# ShieldArduino_Due_5.net
KiCad netlist of a schematic drawn in Altium Designer
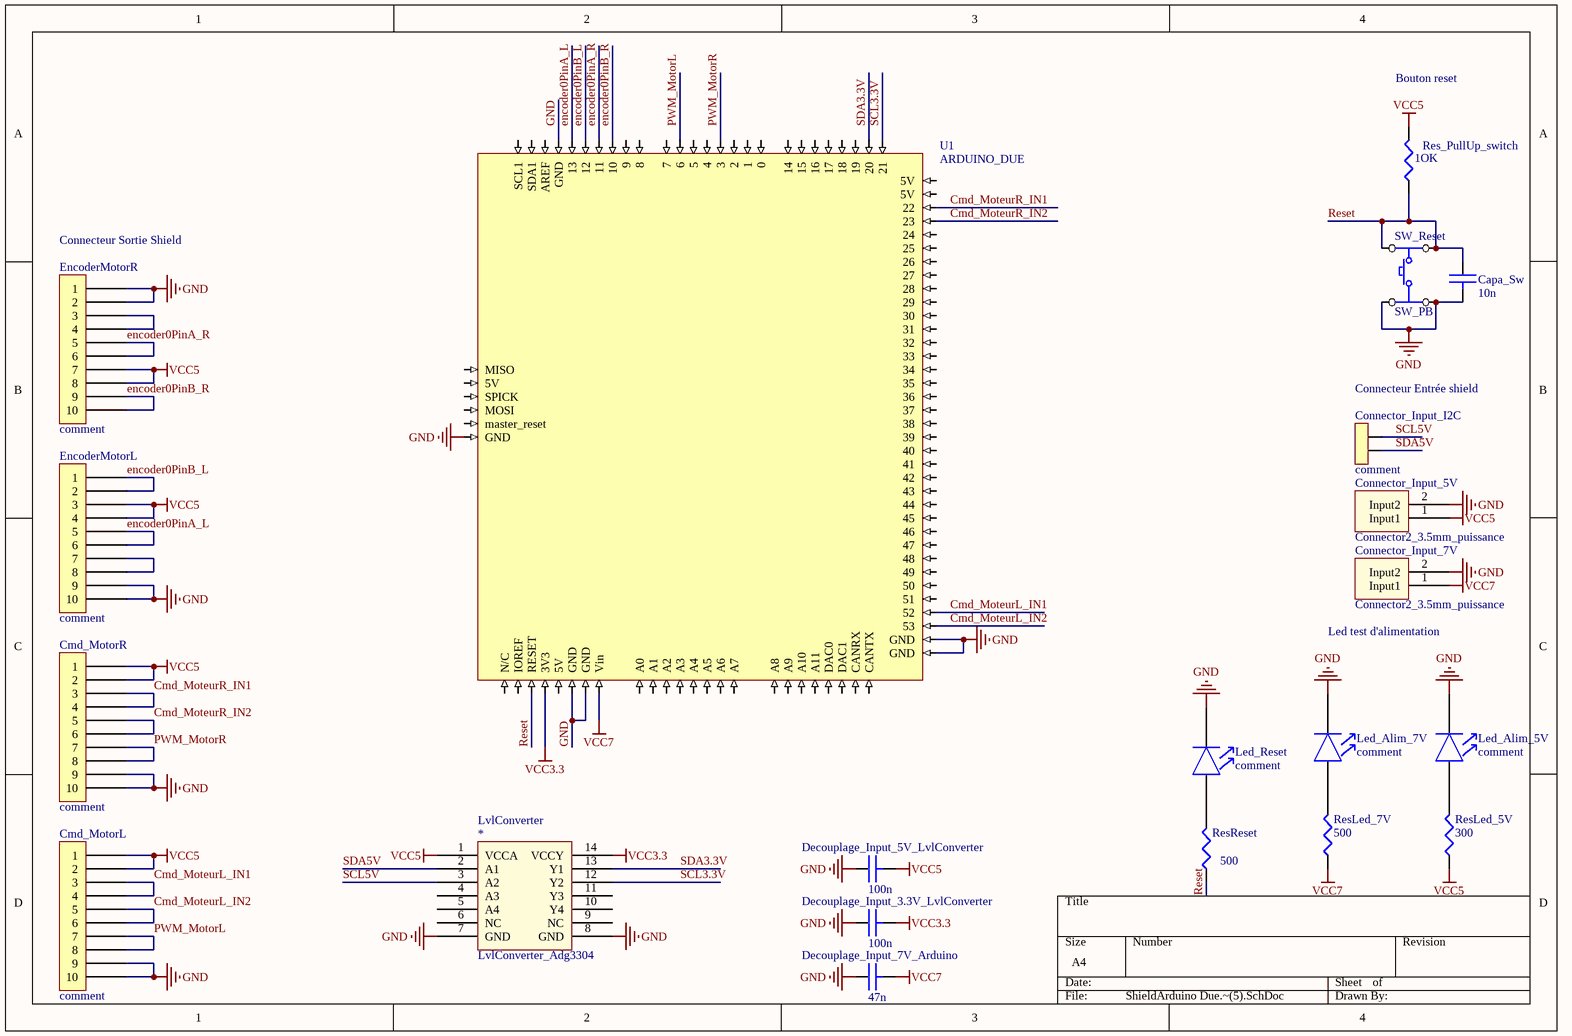
[diagram p0: ShieldArduino Due.~(5).SchDoc]

(export (version "E")
  (design (tool "Eeschema 10.0.6"))
  (components
    (comp (ref "*")
      (value "LvlConverter_Adg3304")
      (footprint "LvlConverter_Adg3304")
      (libsource (lib "LvlConverter_Adg3304") (part "LvlConverter_Adg3304"))
    )
    (comp (ref "Capa_Sw")
      (value "10n")
      (footprint "0805")
      (description "capacité non polarisée")
      (fields (field (name "Comment") "CAP"))
      (libsource (lib "ISEN_basics") (part "CAP"))
    )
    (comp (ref "Cmd_MotorL")
      (value "comment")
      (footprint "HE10-10V")
      (description "10-pin connector")
      (libsource (lib "ISEN_basics") (part "HE10-10"))
    )
    (comp (ref "Cmd_MotorR")
      (value "comment")
      (footprint "HE10-10V")
      (description "10-pin connector")
      (libsource (lib "ISEN_basics") (part "HE10-10"))
    )
    (comp (ref "Connector_Input_5V")
      (value "Connector2_3.5mm_puissance")
      (footprint "Connector2_3.5mm_puissance")
      (libsource (lib "Connector2_3.5mm_puissance") (part "Connector2_3.5mm_puissance"))
    )
    (comp (ref "Connector_Input_7V")
      (value "Connector2_3.5mm_puissance")
      (footprint "Connector2_3.5mm_puissance")
      (libsource (lib "Connector2_3.5mm_puissance") (part "Connector2_3.5mm_puissance"))
    )
    (comp (ref "Connector_Input_I2C")
      (value "comment")
      (footprint "AMP_2")
      (description "connecteur alim 2 pôles")
      (libsource (lib "ISEN_basics") (part "POWER2"))
    )
    (comp (ref "Decouplage_Input_3.3V_LvlConverter")
      (value "100n")
      (footprint "0805")
      (description "capacité non polarisée")
      (fields (field (name "Comment") "CAP"))
      (libsource (lib "ISEN_basics") (part "CAP"))
    )
    (comp (ref "Decouplage_Input_5V_LvlConverter")
      (value "100n")
      (footprint "0805")
      (description "capacité non polarisée")
      (fields (field (name "Comment") "CAP"))
      (libsource (lib "ISEN_basics") (part "CAP"))
    )
    (comp (ref "Decouplage_Input_7V_Arduino")
      (value "47n")
      (footprint "0805")
      (description "capacité non polarisée")
      (fields (field (name "Comment") "CAP"))
      (libsource (lib "ISEN_basics") (part "CAP"))
    )
    (comp (ref "EncoderMotorL")
      (value "comment")
      (footprint "HE10-10V")
      (description "10-pin connector")
      (libsource (lib "ISEN_basics") (part "HE10-10"))
    )
    (comp (ref "EncoderMotorR")
      (value "comment")
      (footprint "HE10-10V")
      (description "10-pin connector")
      (libsource (lib "ISEN_basics") (part "HE10-10"))
    )
    (comp (ref "Led_Alim_5V")
      (value "comment")
      (footprint "LED0805")
      (description "LED 5mm/3mm/CMS")
      (libsource (lib "ISEN_basics") (part "LED"))
    )
    (comp (ref "Led_Alim_7V")
      (value "comment")
      (footprint "LED0805")
      (description "LED 5mm/3mm/CMS")
      (libsource (lib "ISEN_basics") (part "LED"))
    )
    (comp (ref "Led_Reset")
      (value "comment")
      (footprint "LED0805")
      (description "LED 5mm/3mm/CMS")
      (libsource (lib "ISEN_basics") (part "LED"))
    )
    (comp (ref "ResLed_5V")
      (value "300")
      (footprint "0805")
      (description "resistance")
      (fields (field (name "Comment") "RES"))
      (libsource (lib "ISEN_basics") (part "RES"))
    )
    (comp (ref "ResLed_7V")
      (value "500")
      (footprint "0805")
      (description "resistance")
      (fields (field (name "Comment") "RES"))
      (libsource (lib "ISEN_basics") (part "RES"))
    )
    (comp (ref "ResReset")
      (value "500")
      (footprint "0805")
      (description "resistance")
      (fields (field (name "Comment") "RES"))
      (libsource (lib "ISEN_basics") (part "RES"))
    )
    (comp (ref "Res_PullUp_switch")
      (value "1OK")
      (footprint "0805")
      (description "resistance")
      (fields (field (name "Comment") "RES"))
      (libsource (lib "ISEN_basics") (part "RES"))
    )
    (comp (ref "SW_Reset") (value "SW_PB") (footprint "KSA") (libsource (lib "ISEN_basics") (part "SW_PB")))
    (comp (ref "U1")
      (value "ARDUINO_DUE")
      (footprint "ARDUINO_DUE")
      (libsource (lib "ISEN_basics") (part "ARDUINO_DUE"))
    )
  )
  (nets
    (net (code "1") (name "/Cmd_MoteurL_IN1") (class "Default")
      (node (ref "Cmd_MotorL") (pin "3") (pinfunction "3_3") (pintype "passive"))
      (node (ref "Cmd_MotorL") (pin "4") (pinfunction "4_4") (pintype "passive"))
      (node (ref "U1") (pin "59") (pinfunction "52_59") (pintype "input"))
    )
    (net (code "2") (name "/Cmd_MoteurL_IN2") (class "Default")
      (node (ref "Cmd_MotorL") (pin "5") (pinfunction "5_5") (pintype "passive"))
      (node (ref "Cmd_MotorL") (pin "6") (pinfunction "6_6") (pintype "passive"))
      (node (ref "U1") (pin "60") (pinfunction "53_60") (pintype "input"))
    )
    (net (code "3") (name "/Cmd_MoteurR_IN1") (class "Default")
      (node (ref "Cmd_MotorR") (pin "3") (pinfunction "3_3") (pintype "passive"))
      (node (ref "Cmd_MotorR") (pin "4") (pinfunction "4_4") (pintype "passive"))
      (node (ref "U1") (pin "29") (pinfunction "22_29") (pintype "input"))
    )
    (net (code "4") (name "/Cmd_MoteurR_IN2") (class "Default")
      (node (ref "Cmd_MotorR") (pin "5") (pinfunction "5_5") (pintype "passive"))
      (node (ref "Cmd_MotorR") (pin "6") (pinfunction "6_6") (pintype "passive"))
      (node (ref "U1") (pin "30") (pinfunction "23_30") (pintype "input"))
    )
    (net (code "5") (name "/PWM_MotorL") (class "Default")
      (node (ref "Cmd_MotorL") (pin "7") (pinfunction "7_7") (pintype "passive"))
      (node (ref "Cmd_MotorL") (pin "8") (pinfunction "8_8") (pintype "passive"))
      (node (ref "U1") (pin "12") (pinfunction "6_12") (pintype "input"))
    )
    (net (code "6") (name "/PWM_MotorR") (class "Default")
      (node (ref "Cmd_MotorR") (pin "7") (pinfunction "7_7") (pintype "passive"))
      (node (ref "Cmd_MotorR") (pin "8") (pinfunction "8_8") (pintype "passive"))
      (node (ref "U1") (pin "15") (pinfunction "3_15") (pintype "input"))
    )
    (net (code "7") (name "/Reset") (class "Default")
      (node (ref "Capa_Sw") (pin "1") (pinfunction "1_1") (pintype "passive"))
      (node (ref "ResReset") (pin "1") (pintype "passive"))
      (node (ref "Res_PullUp_switch") (pin "1") (pintype "passive"))
      (node (ref "SW_Reset") (pin "3") (pintype "passive"))
      (node (ref "SW_Reset") (pin "4") (pintype "passive"))
      (node (ref "U1") (pin "84") (pinfunction "RESET_84") (pintype "input"))
    )
    (net (code "8") (name "/SCL3.3V") (class "Default")
      (node (ref "*") (pin "12") (pinfunction "Y2_12") (pintype "power_in"))
      (node (ref "U1") (pin "26") (pinfunction "21_26") (pintype "input"))
    )
    (net (code "9") (name "/SCL5V") (class "Default")
      (node (ref "*") (pin "3") (pinfunction "A2_3") (pintype "power_in"))
      (node (ref "Connector_Input_I2C") (pin "1") (pintype "passive"))
    )
    (net (code "10") (name "/SDA3.3V") (class "Default")
      (node (ref "*") (pin "13") (pinfunction "Y1_13") (pintype "power_in"))
      (node (ref "U1") (pin "25") (pinfunction "20_25") (pintype "input"))
    )
    (net (code "11") (name "/SDA5V") (class "Default")
      (node (ref "*") (pin "2") (pinfunction "A1_2") (pintype "power_in"))
      (node (ref "Connector_Input_I2C") (pin "2") (pintype "passive"))
    )
    (net (code "12") (name "/encoder0PinA_L") (class "Default")
      (node (ref "EncoderMotorL") (pin "5") (pinfunction "5_5") (pintype "passive"))
      (node (ref "EncoderMotorL") (pin "6") (pinfunction "6_6") (pintype "passive"))
      (node (ref "U1") (pin "5") (pinfunction "13_5") (pintype "input"))
    )
    (net (code "13") (name "/encoder0PinA_R") (class "Default")
      (node (ref "EncoderMotorR") (pin "5") (pinfunction "5_5") (pintype "passive"))
      (node (ref "EncoderMotorR") (pin "6") (pinfunction "6_6") (pintype "passive"))
      (node (ref "U1") (pin "7") (pinfunction "11_7") (pintype "input"))
    )
    (net (code "14") (name "/encoder0PinB_L") (class "Default")
      (node (ref "EncoderMotorL") (pin "1") (pinfunction "1_1") (pintype "passive"))
      (node (ref "EncoderMotorL") (pin "2") (pinfunction "2_2") (pintype "passive"))
      (node (ref "U1") (pin "6") (pinfunction "12_6") (pintype "input"))
    )
    (net (code "15") (name "/encoder0PinB_R") (class "Default")
      (node (ref "EncoderMotorR") (pin "10") (pinfunction "10_10") (pintype "passive"))
      (node (ref "EncoderMotorR") (pin "9") (pinfunction "9_9") (pintype "passive"))
      (node (ref "U1") (pin "8") (pinfunction "10_8") (pintype "input"))
    )
    (net (code "16") (name "GND") (class "Default")
      (node (ref "*") (pin "7") (pinfunction "GND_7") (pintype "power_in"))
      (node (ref "*") (pin "8") (pinfunction "GND_8") (pintype "power_in"))
      (node (ref "Capa_Sw") (pin "2") (pinfunction "2_2") (pintype "passive"))
      (node (ref "Cmd_MotorL") (pin "10") (pinfunction "10_10") (pintype "passive"))
      (node (ref "Cmd_MotorL") (pin "9") (pinfunction "9_9") (pintype "passive"))
      (node (ref "Cmd_MotorR") (pin "10") (pinfunction "10_10") (pintype "passive"))
      (node (ref "Cmd_MotorR") (pin "9") (pinfunction "9_9") (pintype "passive"))
      (node (ref "Connector_Input_5V") (pin "2") (pinfunction "Input2_2") (pintype "power_in"))
      (node (ref "Connector_Input_7V") (pin "2") (pinfunction "Input2_2") (pintype "power_in"))
      (node (ref "Decouplage_Input_3.3V_LvlConverter") (pin "1") (pinfunction "1_1") (pintype "passive"))
      (node (ref "Decouplage_Input_5V_LvlConverter") (pin "1") (pinfunction "1_1") (pintype "passive"))
      (node (ref "Decouplage_Input_7V_Arduino") (pin "1") (pinfunction "1_1") (pintype "passive"))
      (node (ref "EncoderMotorL") (pin "10") (pinfunction "10_10") (pintype "passive"))
      (node (ref "EncoderMotorL") (pin "9") (pinfunction "9_9") (pintype "passive"))
      (node (ref "EncoderMotorR") (pin "1") (pinfunction "1_1") (pintype "passive"))
      (node (ref "EncoderMotorR") (pin "2") (pinfunction "2_2") (pintype "passive"))
      (node (ref "Led_Alim_5V") (pin "K") (pinfunction "10_K") (pintype "passive"))
      (node (ref "Led_Alim_7V") (pin "K") (pinfunction "10_K") (pintype "passive"))
      (node (ref "Led_Reset") (pin "K") (pinfunction "10_K") (pintype "passive"))
      (node (ref "SW_Reset") (pin "1") (pintype "passive"))
      (node (ref "SW_Reset") (pin "2") (pintype "passive"))
      (node (ref "U1") (pin "4") (pinfunction "GND_4") (pintype "input"))
      (node (ref "U1") (pin "61") (pinfunction "GND_61") (pintype "input"))
      (node (ref "U1") (pin "62") (pinfunction "GND_62") (pintype "input"))
      (node (ref "U1") (pin "80") (pinfunction "GND_80") (pintype "input"))
      (node (ref "U1") (pin "81") (pinfunction "GND_81") (pintype "input"))
      (node (ref "U1") (pin "92") (pinfunction "GND_92") (pintype "input"))
    )
    (net (code "17") (name "Net-(EncoderMotorL-Pad7)") (class "Default")
      (node (ref "EncoderMotorL") (pin "7") (pinfunction "7_7") (pintype "passive"))
      (node (ref "EncoderMotorL") (pin "8") (pinfunction "8_8") (pintype "passive"))
    )
    (net (code "18") (name "Net-(EncoderMotorR-Pad3)") (class "Default")
      (node (ref "EncoderMotorR") (pin "3") (pinfunction "3_3") (pintype "passive"))
      (node (ref "EncoderMotorR") (pin "4") (pinfunction "4_4") (pintype "passive"))
    )
    (net (code "19") (name "Net-(Led_Alim_5V-8)") (class "Default")
      (node (ref "Led_Alim_5V") (pin "A") (pinfunction "8_A") (pintype "passive"))
      (node (ref "ResLed_5V") (pin "2") (pintype "passive"))
    )
    (net (code "20") (name "Net-(Led_Alim_7V-8)") (class "Default")
      (node (ref "Led_Alim_7V") (pin "A") (pinfunction "8_A") (pintype "passive"))
      (node (ref "ResLed_7V") (pin "2") (pintype "passive"))
    )
    (net (code "21") (name "Net-(Led_Reset-8)") (class "Default")
      (node (ref "Led_Reset") (pin "A") (pinfunction "8_A") (pintype "passive"))
      (node (ref "ResReset") (pin "2") (pintype "passive"))
    )
    (net (code "22") (name "VCC3.3") (class "Default")
      (node (ref "*") (pin "14") (pinfunction "VCCY_14") (pintype "power_in"))
      (node (ref "Decouplage_Input_3.3V_LvlConverter") (pin "2") (pinfunction "2_2") (pintype "passive"))
      (node (ref "U1") (pin "83") (pinfunction "3V3_83") (pintype "input"))
    )
    (net (code "23") (name "VCC5") (class "Default")
      (node (ref "*") (pin "1") (pinfunction "VCCA_1") (pintype "power_in"))
      (node (ref "Cmd_MotorL") (pin "1") (pinfunction "1_1") (pintype "passive"))
      (node (ref "Cmd_MotorL") (pin "2") (pinfunction "2_2") (pintype "passive"))
      (node (ref "Cmd_MotorR") (pin "1") (pinfunction "1_1") (pintype "passive"))
      (node (ref "Cmd_MotorR") (pin "2") (pinfunction "2_2") (pintype "passive"))
      (node (ref "Connector_Input_5V") (pin "1") (pinfunction "Input1_1") (pintype "power_in"))
      (node (ref "Decouplage_Input_5V_LvlConverter") (pin "2") (pinfunction "2_2") (pintype "passive"))
      (node (ref "EncoderMotorL") (pin "3") (pinfunction "3_3") (pintype "passive"))
      (node (ref "EncoderMotorL") (pin "4") (pinfunction "4_4") (pintype "passive"))
      (node (ref "EncoderMotorR") (pin "7") (pinfunction "7_7") (pintype "passive"))
      (node (ref "EncoderMotorR") (pin "8") (pinfunction "8_8") (pintype "passive"))
      (node (ref "ResLed_5V") (pin "1") (pintype "passive"))
      (node (ref "Res_PullUp_switch") (pin "2") (pintype "passive"))
    )
    (net (code "24") (name "VCC7") (class "Default")
      (node (ref "Connector_Input_7V") (pin "1") (pinfunction "Input1_1") (pintype "power_in"))
      (node (ref "Decouplage_Input_7V_Arduino") (pin "2") (pinfunction "2_2") (pintype "passive"))
      (node (ref "ResLed_7V") (pin "1") (pintype "passive"))
      (node (ref "U1") (pin "79") (pinfunction "Vin_79") (pintype "input"))
    )
    (net (code "25") (name "unconnected-(*-A3-Pad4)") (class "Default")
      (node (ref "*") (pin "4") (pinfunction "A3_4") (pintype "power_in"))
    )
    (net (code "26") (name "unconnected-(*-A4-Pad5)") (class "Default")
      (node (ref "*") (pin "5") (pinfunction "A4_5") (pintype "power_in"))
    )
    (net (code "27") (name "unconnected-(*-NC-Pad6)") (class "Default")
      (node (ref "*") (pin "6") (pinfunction "NC_6") (pintype "power_in"))
    )
    (net (code "28") (name "unconnected-(*-NC-Pad9)") (class "Default")
      (node (ref "*") (pin "9") (pinfunction "NC_9") (pintype "power_in"))
    )
    (net (code "29") (name "unconnected-(*-Y3-Pad11)") (class "Default")
      (node (ref "*") (pin "11") (pinfunction "Y3_11") (pintype "power_in"))
    )
    (net (code "30") (name "unconnected-(*-Y4-Pad10)") (class "Default")
      (node (ref "*") (pin "10") (pinfunction "Y4_10") (pintype "power_in"))
    )
    (net (code "31") (name "unconnected-(U1-0-Pad18)") (class "Default")
      (node (ref "U1") (pin "18") (pinfunction "0_18") (pintype "input"))
    )
    (net (code "32") (name "unconnected-(U1-1-Pad17)") (class "Default")
      (node (ref "U1") (pin "17") (pinfunction "1_17") (pintype "input"))
    )
    (net (code "33") (name "unconnected-(U1-2-Pad16)") (class "Default")
      (node (ref "U1") (pin "16") (pinfunction "2_16") (pintype "input"))
    )
    (net (code "34") (name "unconnected-(U1-4-Pad14)") (class "Default")
      (node (ref "U1") (pin "14") (pinfunction "4_14") (pintype "input"))
    )
    (net (code "35") (name "unconnected-(U1-5-Pad13)") (class "Default")
      (node (ref "U1") (pin "13") (pinfunction "5_13") (pintype "input"))
    )
    (net (code "36") (name "unconnected-(U1-5V-Pad27)") (class "Default")
      (node (ref "U1") (pin "27") (pinfunction "5V_27") (pintype "input"))
    )
    (net (code "37") (name "unconnected-(U1-5V-Pad28)") (class "Default")
      (node (ref "U1") (pin "28") (pinfunction "5V_28") (pintype "input"))
    )
    (net (code "38") (name "unconnected-(U1-5V-Pad82)") (class "Default")
      (node (ref "U1") (pin "82") (pinfunction "5V_82") (pintype "input"))
    )
    (net (code "39") (name "unconnected-(U1-5V-Pad88)") (class "Default")
      (node (ref "U1") (pin "88") (pinfunction "5V_88") (pintype "input"))
    )
    (net (code "40") (name "unconnected-(U1-7-Pad11)") (class "Default")
      (node (ref "U1") (pin "11") (pinfunction "7_11") (pintype "input"))
    )
    (net (code "41") (name "unconnected-(U1-8-Pad10)") (class "Default")
      (node (ref "U1") (pin "10") (pinfunction "8_10") (pintype "input"))
    )
    (net (code "42") (name "unconnected-(U1-14-Pad19)") (class "Default")
      (node (ref "U1") (pin "19") (pinfunction "14_19") (pintype "input"))
    )
    (net (code "43") (name "unconnected-(U1-15-Pad20)") (class "Default")
      (node (ref "U1") (pin "20") (pinfunction "15_20") (pintype "input"))
    )
    (net (code "44") (name "unconnected-(U1-16-Pad21)") (class "Default")
      (node (ref "U1") (pin "21") (pinfunction "16_21") (pintype "input"))
    )
    (net (code "45") (name "unconnected-(U1-17-Pad22)") (class "Default")
      (node (ref "U1") (pin "22") (pinfunction "17_22") (pintype "input"))
    )
    (net (code "46") (name "unconnected-(U1-18-Pad23)") (class "Default")
      (node (ref "U1") (pin "23") (pinfunction "18_23") (pintype "input"))
    )
    (net (code "47") (name "unconnected-(U1-19-Pad24)") (class "Default")
      (node (ref "U1") (pin "24") (pinfunction "19_24") (pintype "input"))
    )
    (net (code "48") (name "unconnected-(U1-24-Pad31)") (class "Default")
      (node (ref "U1") (pin "31") (pinfunction "24_31") (pintype "input"))
    )
    (net (code "49") (name "unconnected-(U1-25-Pad32)") (class "Default")
      (node (ref "U1") (pin "32") (pinfunction "25_32") (pintype "input"))
    )
    (net (code "50") (name "unconnected-(U1-26-Pad33)") (class "Default")
      (node (ref "U1") (pin "33") (pinfunction "26_33") (pintype "input"))
    )
    (net (code "51") (name "unconnected-(U1-27-Pad34)") (class "Default")
      (node (ref "U1") (pin "34") (pinfunction "27_34") (pintype "input"))
    )
    (net (code "52") (name "unconnected-(U1-28-Pad35)") (class "Default")
      (node (ref "U1") (pin "35") (pinfunction "28_35") (pintype "input"))
    )
    (net (code "53") (name "unconnected-(U1-29-Pad36)") (class "Default")
      (node (ref "U1") (pin "36") (pinfunction "29_36") (pintype "input"))
    )
    (net (code "54") (name "unconnected-(U1-30-Pad37)") (class "Default")
      (node (ref "U1") (pin "37") (pinfunction "30_37") (pintype "input"))
    )
    (net (code "55") (name "unconnected-(U1-31-Pad38)") (class "Default")
      (node (ref "U1") (pin "38") (pinfunction "31_38") (pintype "input"))
    )
    (net (code "56") (name "unconnected-(U1-32-Pad39)") (class "Default")
      (node (ref "U1") (pin "39") (pinfunction "32_39") (pintype "input"))
    )
    (net (code "57") (name "unconnected-(U1-33-Pad40)") (class "Default")
      (node (ref "U1") (pin "40") (pinfunction "33_40") (pintype "input"))
    )
    (net (code "58") (name "unconnected-(U1-34-Pad41)") (class "Default")
      (node (ref "U1") (pin "41") (pinfunction "34_41") (pintype "input"))
    )
    (net (code "59") (name "unconnected-(U1-35-Pad42)") (class "Default")
      (node (ref "U1") (pin "42") (pinfunction "35_42") (pintype "input"))
    )
    (net (code "60") (name "unconnected-(U1-36-Pad43)") (class "Default")
      (node (ref "U1") (pin "43") (pinfunction "36_43") (pintype "input"))
    )
    (net (code "61") (name "unconnected-(U1-37-Pad44)") (class "Default")
      (node (ref "U1") (pin "44") (pinfunction "37_44") (pintype "input"))
    )
    (net (code "62") (name "unconnected-(U1-38-Pad45)") (class "Default")
      (node (ref "U1") (pin "45") (pinfunction "38_45") (pintype "input"))
    )
    (net (code "63") (name "unconnected-(U1-39-Pad46)") (class "Default")
      (node (ref "U1") (pin "46") (pinfunction "39_46") (pintype "input"))
    )
    (net (code "64") (name "unconnected-(U1-40-Pad47)") (class "Default")
      (node (ref "U1") (pin "47") (pinfunction "40_47") (pintype "input"))
    )
    (net (code "65") (name "unconnected-(U1-41-Pad48)") (class "Default")
      (node (ref "U1") (pin "48") (pinfunction "41_48") (pintype "input"))
    )
    (net (code "66") (name "unconnected-(U1-42-Pad49)") (class "Default")
      (node (ref "U1") (pin "49") (pinfunction "42_49") (pintype "input"))
    )
    (net (code "67") (name "unconnected-(U1-43-Pad50)") (class "Default")
      (node (ref "U1") (pin "50") (pinfunction "43_50") (pintype "input"))
    )
    (net (code "68") (name "unconnected-(U1-44-Pad51)") (class "Default")
      (node (ref "U1") (pin "51") (pinfunction "44_51") (pintype "input"))
    )
    (net (code "69") (name "unconnected-(U1-45-Pad52)") (class "Default")
      (node (ref "U1") (pin "52") (pinfunction "45_52") (pintype "input"))
    )
    (net (code "70") (name "unconnected-(U1-46-Pad53)") (class "Default")
      (node (ref "U1") (pin "53") (pinfunction "46_53") (pintype "input"))
    )
    (net (code "71") (name "unconnected-(U1-47-Pad54)") (class "Default")
      (node (ref "U1") (pin "54") (pinfunction "47_54") (pintype "input"))
    )
    (net (code "72") (name "unconnected-(U1-48-Pad55)") (class "Default")
      (node (ref "U1") (pin "55") (pinfunction "48_55") (pintype "input"))
    )
    (net (code "73") (name "unconnected-(U1-49-Pad56)") (class "Default")
      (node (ref "U1") (pin "56") (pinfunction "49_56") (pintype "input"))
    )
    (net (code "74") (name "unconnected-(U1-50-Pad57)") (class "Default")
      (node (ref "U1") (pin "57") (pinfunction "50_57") (pintype "input"))
    )
    (net (code "75") (name "unconnected-(U1-51-Pad58)") (class "Default")
      (node (ref "U1") (pin "58") (pinfunction "51_58") (pintype "input"))
    )
    (net (code "76") (name "unconnected-(U1-A0-Pad78)") (class "Default")
      (node (ref "U1") (pin "78") (pinfunction "A0_78") (pintype "input"))
    )
    (net (code "77") (name "unconnected-(U1-A1-Pad77)") (class "Default")
      (node (ref "U1") (pin "77") (pinfunction "A1_77") (pintype "input"))
    )
    (net (code "78") (name "unconnected-(U1-A2-Pad76)") (class "Default")
      (node (ref "U1") (pin "76") (pinfunction "A2_76") (pintype "input"))
    )
    (net (code "79") (name "unconnected-(U1-A3-Pad75)") (class "Default")
      (node (ref "U1") (pin "75") (pinfunction "A3_75") (pintype "input"))
    )
    (net (code "80") (name "unconnected-(U1-A4-Pad74)") (class "Default")
      (node (ref "U1") (pin "74") (pinfunction "A4_74") (pintype "input"))
    )
    (net (code "81") (name "unconnected-(U1-A5-Pad73)") (class "Default")
      (node (ref "U1") (pin "73") (pinfunction "A5_73") (pintype "input"))
    )
    (net (code "82") (name "unconnected-(U1-A6-Pad72)") (class "Default")
      (node (ref "U1") (pin "72") (pinfunction "A6_72") (pintype "input"))
    )
    (net (code "83") (name "unconnected-(U1-A7-Pad71)") (class "Default")
      (node (ref "U1") (pin "71") (pinfunction "A7_71") (pintype "input"))
    )
    (net (code "84") (name "unconnected-(U1-A8-Pad70)") (class "Default")
      (node (ref "U1") (pin "70") (pinfunction "A8_70") (pintype "input"))
    )
    (net (code "85") (name "unconnected-(U1-A9-Pad69)") (class "Default")
      (node (ref "U1") (pin "69") (pinfunction "A9_69") (pintype "input"))
    )
    (net (code "86") (name "unconnected-(U1-A10-Pad68)") (class "Default")
      (node (ref "U1") (pin "68") (pinfunction "A10_68") (pintype "input"))
    )
    (net (code "87") (name "unconnected-(U1-A11-Pad67)") (class "Default")
      (node (ref "U1") (pin "67") (pinfunction "A11_67") (pintype "input"))
    )
    (net (code "88") (name "unconnected-(U1-AREF-Pad3)") (class "Default")
      (node (ref "U1") (pin "3") (pinfunction "AREF_3") (pintype "input"))
    )
    (net (code "89") (name "unconnected-(U1-CANRX-Pad64)") (class "Default")
      (node (ref "U1") (pin "64") (pinfunction "CANRX_64") (pintype "input"))
    )
    (net (code "90") (name "unconnected-(U1-CANTX-Pad63)") (class "Default")
      (node (ref "U1") (pin "63") (pinfunction "CANTX_63") (pintype "input"))
    )
    (net (code "91") (name "unconnected-(U1-DAC0-Pad66)") (class "Default")
      (node (ref "U1") (pin "66") (pinfunction "DAC0_66") (pintype "input"))
    )
    (net (code "92") (name "unconnected-(U1-DAC1-Pad65)") (class "Default")
      (node (ref "U1") (pin "65") (pinfunction "DAC1_65") (pintype "input"))
    )
    (net (code "93") (name "unconnected-(U1-IOREF-Pad85)") (class "Default")
      (node (ref "U1") (pin "85") (pinfunction "IOREF_85") (pintype "input"))
    )
    (net (code "94") (name "unconnected-(U1-MISO-Pad87)") (class "Default")
      (node (ref "U1") (pin "87") (pinfunction "MISO_87") (pintype "input"))
    )
    (net (code "95") (name "unconnected-(U1-MOSI-Pad90)") (class "Default")
      (node (ref "U1") (pin "90") (pinfunction "MOSI_90") (pintype "input"))
    )
    (net (code "96") (name "unconnected-(U1-N{slash}C-Pad86)") (class "Default")
      (node (ref "U1") (pin "86") (pinfunction "N/C_86") (pintype "input"))
    )
    (net (code "97") (name "unconnected-(U1-Pad9)") (class "Default")
      (node (ref "U1") (pin "9") (pinfunction "9_9") (pintype "input"))
    )
    (net (code "98") (name "unconnected-(U1-SCL1-Pad1)") (class "Default")
      (node (ref "U1") (pin "1") (pinfunction "SCL1_1") (pintype "input"))
    )
    (net (code "99") (name "unconnected-(U1-SDA1-Pad2)") (class "Default")
      (node (ref "U1") (pin "2") (pinfunction "SDA1_2") (pintype "input"))
    )
    (net (code "100") (name "unconnected-(U1-SPICK-Pad89)") (class "Default")
      (node (ref "U1") (pin "89") (pinfunction "SPICK_89") (pintype "input"))
    )
    (net (code "101") (name "unconnected-(U1-master_reset-Pad91)") (class "Default")
      (node (ref "U1") (pin "91") (pinfunction "master_reset_91") (pintype "input"))
    )
  )
)
